# EN715_ExpansionBoard_ver1_1.net
KiCad netlist of a schematic drawn in EAGLE
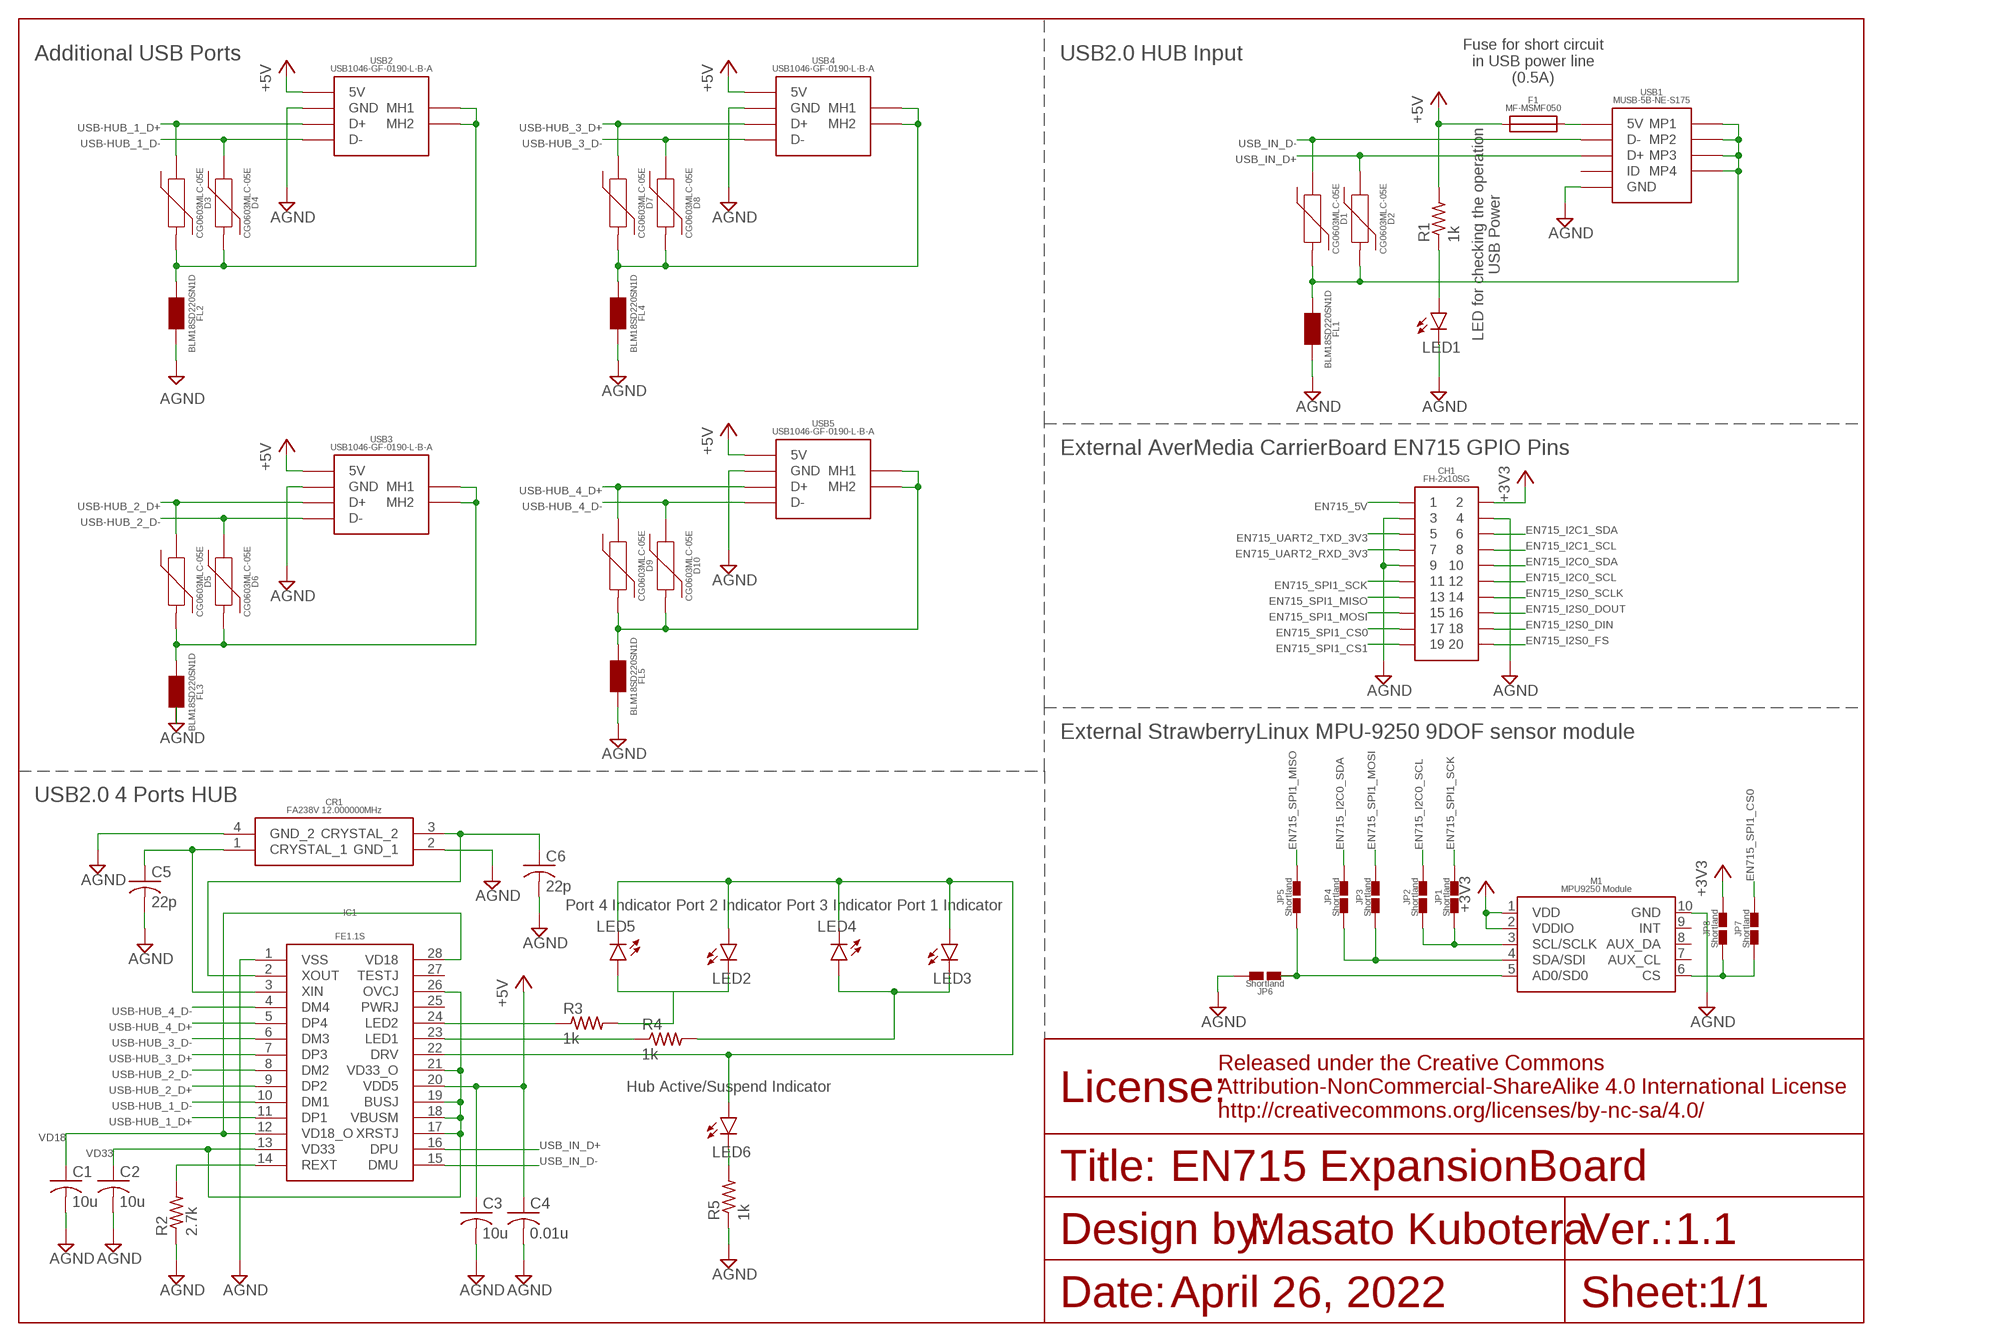
[diagram p0: schematic, sheet 1]

(export (version "E")
  (design (tool "Eeschema 10.0.6"))
  (components
    (comp (ref "C1")
      (value "10u")
      (footprint "eagle-import:C0603")
      (libsource (lib "eagle-import") (part "C-USC0603"))
    )
    (comp (ref "C2")
      (value "10u")
      (footprint "eagle-import:C0603")
      (libsource (lib "eagle-import") (part "C-USC0603"))
    )
    (comp (ref "C3")
      (value "10u")
      (footprint "eagle-import:C0603")
      (libsource (lib "eagle-import") (part "C-USC0603"))
    )
    (comp (ref "C4")
      (value "0.01u")
      (footprint "eagle-import:C0603")
      (libsource (lib "eagle-import") (part "C-USC0603"))
    )
    (comp (ref "C5")
      (value "22p")
      (footprint "eagle-import:C0603")
      (libsource (lib "eagle-import") (part "C-USC0603"))
    )
    (comp (ref "C6")
      (value "22p")
      (footprint "eagle-import:C0603")
      (libsource (lib "eagle-import") (part "C-USC0603"))
    )
    (comp (ref "CH1")
      (value "2X10")
      (footprint "eagle-import:2X10")
      (libsource (lib "eagle-import") (part "2X10"))
    )
    (comp (ref "CR1")
      (value "FA238V_12.000000MHZ")
      (footprint "eagle-import:FA238V")
      (libsource (lib "eagle-import") (part "FA238V_12.000000MHZ"))
    )
    (comp (ref "D1")
      (value "CG0603MLC-05E")
      (footprint "eagle-import:CG0603MLC-05E")
      (libsource (lib "eagle-import") (part "CG0603MLC-05E"))
    )
    (comp (ref "D2")
      (value "CG0603MLC-05E")
      (footprint "eagle-import:CG0603MLC-05E")
      (libsource (lib "eagle-import") (part "CG0603MLC-05E"))
    )
    (comp (ref "D3")
      (value "CG0603MLC-05E")
      (footprint "eagle-import:CG0603MLC-05E")
      (libsource (lib "eagle-import") (part "CG0603MLC-05E"))
    )
    (comp (ref "D4")
      (value "CG0603MLC-05E")
      (footprint "eagle-import:CG0603MLC-05E")
      (libsource (lib "eagle-import") (part "CG0603MLC-05E"))
    )
    (comp (ref "D5")
      (value "CG0603MLC-05E")
      (footprint "eagle-import:CG0603MLC-05E")
      (libsource (lib "eagle-import") (part "CG0603MLC-05E"))
    )
    (comp (ref "D6")
      (value "CG0603MLC-05E")
      (footprint "eagle-import:CG0603MLC-05E")
      (libsource (lib "eagle-import") (part "CG0603MLC-05E"))
    )
    (comp (ref "D7")
      (value "CG0603MLC-05E")
      (footprint "eagle-import:CG0603MLC-05E")
      (libsource (lib "eagle-import") (part "CG0603MLC-05E"))
    )
    (comp (ref "D8")
      (value "CG0603MLC-05E")
      (footprint "eagle-import:CG0603MLC-05E")
      (libsource (lib "eagle-import") (part "CG0603MLC-05E"))
    )
    (comp (ref "D9")
      (value "CG0603MLC-05E")
      (footprint "eagle-import:CG0603MLC-05E")
      (libsource (lib "eagle-import") (part "CG0603MLC-05E"))
    )
    (comp (ref "D10")
      (value "CG0603MLC-05E")
      (footprint "eagle-import:CG0603MLC-05E")
      (libsource (lib "eagle-import") (part "CG0603MLC-05E"))
    )
    (comp (ref "F1")
      (value "MF-MSMF050")
      (footprint "eagle-import:MF-MSMF050")
      (libsource (lib "eagle-import") (part "MF-MSMF050"))
    )
    (comp (ref "FL1")
      (value "BLM18SD220SN1D")
      (footprint "eagle-import:BLM18SD220SN1D")
      (libsource (lib "eagle-import") (part "BLM18SD220SN1D"))
    )
    (comp (ref "FL2")
      (value "BLM18SD220SN1D")
      (footprint "eagle-import:BLM18SD220SN1D")
      (libsource (lib "eagle-import") (part "BLM18SD220SN1D"))
    )
    (comp (ref "FL3")
      (value "BLM18SD220SN1D")
      (footprint "eagle-import:BLM18SD220SN1D")
      (libsource (lib "eagle-import") (part "BLM18SD220SN1D"))
    )
    (comp (ref "FL4")
      (value "BLM18SD220SN1D")
      (footprint "eagle-import:BLM18SD220SN1D")
      (libsource (lib "eagle-import") (part "BLM18SD220SN1D"))
    )
    (comp (ref "FL5")
      (value "BLM18SD220SN1D")
      (footprint "eagle-import:BLM18SD220SN1D")
      (libsource (lib "eagle-import") (part "BLM18SD220SN1D"))
    )
    (comp (ref "IC1")
      (value "FE1.1S")
      (footprint "eagle-import:FE1.1S")
      (libsource (lib "eagle-import") (part "FE1.1S"))
    )
    (comp (ref "JP1")
      (value "SHORTLAND")
      (footprint "eagle-import:SHORTLAND")
      (libsource (lib "eagle-import") (part "SHORTLAND"))
    )
    (comp (ref "JP2")
      (value "SHORTLAND")
      (footprint "eagle-import:SHORTLAND")
      (libsource (lib "eagle-import") (part "SHORTLAND"))
    )
    (comp (ref "JP3")
      (value "SHORTLAND")
      (footprint "eagle-import:SHORTLAND")
      (libsource (lib "eagle-import") (part "SHORTLAND"))
    )
    (comp (ref "JP4")
      (value "SHORTLAND")
      (footprint "eagle-import:SHORTLAND")
      (libsource (lib "eagle-import") (part "SHORTLAND"))
    )
    (comp (ref "JP5")
      (value "SHORTLAND")
      (footprint "eagle-import:SHORTLAND")
      (libsource (lib "eagle-import") (part "SHORTLAND"))
    )
    (comp (ref "JP6")
      (value "SHORTLAND")
      (footprint "eagle-import:SHORTLAND")
      (libsource (lib "eagle-import") (part "SHORTLAND"))
    )
    (comp (ref "JP7")
      (value "SHORTLAND")
      (footprint "eagle-import:SHORTLAND")
      (libsource (lib "eagle-import") (part "SHORTLAND"))
    )
    (comp (ref "JP8")
      (value "SHORTLAND")
      (footprint "eagle-import:SHORTLAND")
      (libsource (lib "eagle-import") (part "SHORTLAND"))
    )
    (comp (ref "LED1")
      (value "LEDSML0603")
      (footprint "eagle-import:SML0603")
      (libsource (lib "eagle-import") (part "LEDSML0603"))
    )
    (comp (ref "LED2")
      (value "LEDSML0603")
      (footprint "eagle-import:SML0603")
      (libsource (lib "eagle-import") (part "LEDSML0603"))
    )
    (comp (ref "LED3")
      (value "LEDSML0603")
      (footprint "eagle-import:SML0603")
      (libsource (lib "eagle-import") (part "LEDSML0603"))
    )
    (comp (ref "LED4")
      (value "LEDSML0603")
      (footprint "eagle-import:SML0603")
      (libsource (lib "eagle-import") (part "LEDSML0603"))
    )
    (comp (ref "LED5")
      (value "LEDSML0603")
      (footprint "eagle-import:SML0603")
      (libsource (lib "eagle-import") (part "LEDSML0603"))
    )
    (comp (ref "LED6")
      (value "LEDSML0603")
      (footprint "eagle-import:SML0603")
      (libsource (lib "eagle-import") (part "LEDSML0603"))
    )
    (comp (ref "M1")
      (value "MPU9250_MODULE")
      (footprint "eagle-import:MPU9250_MODULE")
      (libsource (lib "eagle-import") (part "MPU9250_MODULE"))
    )
    (comp (ref "R1")
      (value "1k")
      (footprint "eagle-import:R0603")
      (libsource (lib "eagle-import") (part "R-US_R0603"))
    )
    (comp (ref "R2")
      (value "2.7k")
      (footprint "eagle-import:R0603")
      (libsource (lib "eagle-import") (part "R-US_R0603"))
    )
    (comp (ref "R3")
      (value "1k")
      (footprint "eagle-import:R0603")
      (libsource (lib "eagle-import") (part "R-US_R0603"))
    )
    (comp (ref "R4")
      (value "1k")
      (footprint "eagle-import:R0603")
      (libsource (lib "eagle-import") (part "R-US_R0603"))
    )
    (comp (ref "R5")
      (value "1k")
      (footprint "eagle-import:R0603")
      (libsource (lib "eagle-import") (part "R-US_R0603"))
    )
    (comp (ref "USB1")
      (value "MINI_USB_B_SMD")
      (footprint "eagle-import:MINI_USB_B_SMD")
      (libsource (lib "eagle-import") (part "MINI_USB_B_SMD"))
    )
    (comp (ref "USB2")
      (value "USB_A_X1_SMD")
      (footprint "eagle-import:USB_A_X1_SMD")
      (libsource (lib "eagle-import") (part "USB_A_X1_SMD"))
    )
    (comp (ref "USB3")
      (value "USB_A_X1_SMD")
      (footprint "eagle-import:USB_A_X1_SMD")
      (libsource (lib "eagle-import") (part "USB_A_X1_SMD"))
    )
    (comp (ref "USB4")
      (value "USB_A_X1_SMD")
      (footprint "eagle-import:USB_A_X1_SMD")
      (libsource (lib "eagle-import") (part "USB_A_X1_SMD"))
    )
    (comp (ref "USB5")
      (value "USB_A_X1_SMD")
      (footprint "eagle-import:USB_A_X1_SMD")
      (libsource (lib "eagle-import") (part "USB_A_X1_SMD"))
    )
  )
  (nets
    (net (code "1") (name "+3V3") (class "Default")
      (node (ref "CH1") (pin "2") (pinfunction "2_2") (pintype "bidirectional"))
      (node (ref "JP8") (pin "2") (pinfunction "2_2") (pintype "bidirectional"))
      (node (ref "M1") (pin "1") (pinfunction "VDD_1") (pintype "bidirectional"))
      (node (ref "M1") (pin "2") (pinfunction "VDDIO_2") (pintype "bidirectional"))
    )
    (net (code "2") (name "+5V") (class "Default")
      (node (ref "C3") (pin "1") (pinfunction "1_1") (pintype "passive"))
      (node (ref "C4") (pin "1") (pinfunction "1_1") (pintype "passive"))
      (node (ref "F1") (pin "1") (pinfunction "1_1") (pintype "bidirectional"))
      (node (ref "IC1") (pin "20") (pinfunction "VDD5_20") (pintype "bidirectional"))
      (node (ref "R1") (pin "2") (pinfunction "2_2") (pintype "passive"))
      (node (ref "USB2") (pin "1") (pinfunction "5V_1") (pintype "bidirectional"))
      (node (ref "USB3") (pin "1") (pinfunction "5V_1") (pintype "bidirectional"))
      (node (ref "USB4") (pin "1") (pinfunction "5V_1") (pintype "bidirectional"))
      (node (ref "USB5") (pin "1") (pinfunction "5V_1") (pintype "bidirectional"))
    )
    (net (code "3") (name "/EN715_5V") (class "Default")
      (node (ref "CH1") (pin "1") (pinfunction "1_1") (pintype "bidirectional"))
    )
    (net (code "4") (name "/EN715_I2C0_SCL") (class "Default")
      (node (ref "CH1") (pin "12") (pinfunction "12_12") (pintype "bidirectional"))
      (node (ref "JP2") (pin "2") (pinfunction "2_2") (pintype "bidirectional"))
    )
    (net (code "5") (name "/EN715_I2C0_SDA") (class "Default")
      (node (ref "CH1") (pin "10") (pinfunction "10_10") (pintype "bidirectional"))
      (node (ref "JP4") (pin "2") (pinfunction "2_2") (pintype "bidirectional"))
    )
    (net (code "6") (name "/EN715_I2C1_SCL") (class "Default")
      (node (ref "CH1") (pin "8") (pinfunction "8_8") (pintype "bidirectional"))
    )
    (net (code "7") (name "/EN715_I2C1_SDA") (class "Default")
      (node (ref "CH1") (pin "6") (pinfunction "6_6") (pintype "bidirectional"))
    )
    (net (code "8") (name "/EN715_I2S0_DIN") (class "Default")
      (node (ref "CH1") (pin "18") (pinfunction "18_18") (pintype "bidirectional"))
    )
    (net (code "9") (name "/EN715_I2S0_DOUT") (class "Default")
      (node (ref "CH1") (pin "16") (pinfunction "16_16") (pintype "bidirectional"))
    )
    (net (code "10") (name "/EN715_I2S0_FS") (class "Default")
      (node (ref "CH1") (pin "20") (pinfunction "20_20") (pintype "bidirectional"))
    )
    (net (code "11") (name "/EN715_I2S0_SCLK") (class "Default")
      (node (ref "CH1") (pin "14") (pinfunction "14_14") (pintype "bidirectional"))
    )
    (net (code "12") (name "/EN715_SPI1_CS0") (class "Default")
      (node (ref "CH1") (pin "17") (pinfunction "17_17") (pintype "bidirectional"))
      (node (ref "JP7") (pin "2") (pinfunction "2_2") (pintype "bidirectional"))
    )
    (net (code "13") (name "/EN715_SPI1_CS1") (class "Default")
      (node (ref "CH1") (pin "19") (pinfunction "19_19") (pintype "bidirectional"))
    )
    (net (code "14") (name "/EN715_SPI1_MISO") (class "Default")
      (node (ref "CH1") (pin "13") (pinfunction "13_13") (pintype "bidirectional"))
      (node (ref "JP5") (pin "2") (pinfunction "2_2") (pintype "bidirectional"))
    )
    (net (code "15") (name "/EN715_SPI1_MOSI") (class "Default")
      (node (ref "CH1") (pin "15") (pinfunction "15_15") (pintype "bidirectional"))
      (node (ref "JP3") (pin "2") (pinfunction "2_2") (pintype "bidirectional"))
    )
    (net (code "16") (name "/EN715_SPI1_SCK") (class "Default")
      (node (ref "CH1") (pin "11") (pinfunction "11_11") (pintype "bidirectional"))
      (node (ref "JP1") (pin "2") (pinfunction "2_2") (pintype "bidirectional"))
    )
    (net (code "17") (name "/EN715_UART2_RXD_3V3") (class "Default")
      (node (ref "CH1") (pin "7") (pinfunction "7_7") (pintype "bidirectional"))
    )
    (net (code "18") (name "/EN715_UART2_TXD_3V3") (class "Default")
      (node (ref "CH1") (pin "5") (pinfunction "5_5") (pintype "bidirectional"))
    )
    (net (code "19") (name "/USB-HUB_1_D+") (class "Default")
      (node (ref "D3") (pin "1") (pinfunction "1_1") (pintype "bidirectional"))
      (node (ref "IC1") (pin "11") (pinfunction "DP1_11") (pintype "bidirectional"))
      (node (ref "USB2") (pin "3") (pinfunction "D+_3") (pintype "bidirectional"))
    )
    (net (code "20") (name "/USB-HUB_1_D-") (class "Default")
      (node (ref "D4") (pin "1") (pinfunction "1_1") (pintype "bidirectional"))
      (node (ref "IC1") (pin "10") (pinfunction "DM1_10") (pintype "bidirectional"))
      (node (ref "USB2") (pin "2") (pinfunction "D-_2") (pintype "bidirectional"))
    )
    (net (code "21") (name "/USB-HUB_2_D+") (class "Default")
      (node (ref "D5") (pin "1") (pinfunction "1_1") (pintype "bidirectional"))
      (node (ref "IC1") (pin "9") (pinfunction "DP2_9") (pintype "bidirectional"))
      (node (ref "USB3") (pin "3") (pinfunction "D+_3") (pintype "bidirectional"))
    )
    (net (code "22") (name "/USB-HUB_2_D-") (class "Default")
      (node (ref "D6") (pin "1") (pinfunction "1_1") (pintype "bidirectional"))
      (node (ref "IC1") (pin "8") (pinfunction "DM2_8") (pintype "bidirectional"))
      (node (ref "USB3") (pin "2") (pinfunction "D-_2") (pintype "bidirectional"))
    )
    (net (code "23") (name "/USB-HUB_3_D+") (class "Default")
      (node (ref "D7") (pin "1") (pinfunction "1_1") (pintype "bidirectional"))
      (node (ref "IC1") (pin "7") (pinfunction "DP3_7") (pintype "bidirectional"))
      (node (ref "USB4") (pin "3") (pinfunction "D+_3") (pintype "bidirectional"))
    )
    (net (code "24") (name "/USB-HUB_3_D-") (class "Default")
      (node (ref "D8") (pin "1") (pinfunction "1_1") (pintype "bidirectional"))
      (node (ref "IC1") (pin "6") (pinfunction "DM3_6") (pintype "bidirectional"))
      (node (ref "USB4") (pin "2") (pinfunction "D-_2") (pintype "bidirectional"))
    )
    (net (code "25") (name "/USB-HUB_4_D+") (class "Default")
      (node (ref "D9") (pin "1") (pinfunction "1_1") (pintype "bidirectional"))
      (node (ref "IC1") (pin "5") (pinfunction "DP4_5") (pintype "bidirectional"))
      (node (ref "USB5") (pin "3") (pinfunction "D+_3") (pintype "bidirectional"))
    )
    (net (code "26") (name "/USB-HUB_4_D-") (class "Default")
      (node (ref "D10") (pin "1") (pinfunction "1_1") (pintype "bidirectional"))
      (node (ref "IC1") (pin "4") (pinfunction "DM4_4") (pintype "bidirectional"))
      (node (ref "USB5") (pin "2") (pinfunction "D-_2") (pintype "bidirectional"))
    )
    (net (code "27") (name "/USB_IN_D+") (class "Default")
      (node (ref "D2") (pin "1") (pinfunction "1_1") (pintype "bidirectional"))
      (node (ref "IC1") (pin "16") (pinfunction "DPU_16") (pintype "bidirectional"))
      (node (ref "USB1") (pin "3") (pinfunction "D+_3") (pintype "bidirectional"))
    )
    (net (code "28") (name "/USB_IN_D-") (class "Default")
      (node (ref "D1") (pin "1") (pinfunction "1_1") (pintype "bidirectional"))
      (node (ref "IC1") (pin "15") (pinfunction "DMU_15") (pintype "bidirectional"))
      (node (ref "USB1") (pin "2") (pinfunction "D-_2") (pintype "bidirectional"))
    )
    (net (code "29") (name "/VD18") (class "Default")
      (node (ref "C1") (pin "1") (pinfunction "1_1") (pintype "passive"))
      (node (ref "IC1") (pin "12") (pinfunction "VD18_O_12") (pintype "bidirectional"))
      (node (ref "IC1") (pin "28") (pinfunction "VD18_28") (pintype "bidirectional"))
    )
    (net (code "30") (name "/VD33") (class "Default")
      (node (ref "C2") (pin "1") (pinfunction "1_1") (pintype "passive"))
      (node (ref "IC1") (pin "13") (pinfunction "VD33_13") (pintype "bidirectional"))
      (node (ref "IC1") (pin "17") (pinfunction "XRSTJ_17") (pintype "bidirectional"))
      (node (ref "IC1") (pin "18") (pinfunction "VBUSM_18") (pintype "bidirectional"))
      (node (ref "IC1") (pin "19") (pinfunction "BUSJ_19") (pintype "bidirectional"))
      (node (ref "IC1") (pin "21") (pinfunction "VD33_O_21") (pintype "bidirectional"))
      (node (ref "IC1") (pin "26") (pinfunction "OVCJ_26") (pintype "bidirectional"))
    )
    (net (code "31") (name "AGND") (class "Default")
      (node (ref "C1") (pin "2") (pinfunction "2_2") (pintype "passive"))
      (node (ref "C2") (pin "2") (pinfunction "2_2") (pintype "passive"))
      (node (ref "C3") (pin "2") (pinfunction "2_2") (pintype "passive"))
      (node (ref "C4") (pin "2") (pinfunction "2_2") (pintype "passive"))
      (node (ref "C5") (pin "2") (pinfunction "2_2") (pintype "passive"))
      (node (ref "C6") (pin "2") (pinfunction "2_2") (pintype "passive"))
      (node (ref "CH1") (pin "3") (pinfunction "3_3") (pintype "bidirectional"))
      (node (ref "CH1") (pin "4") (pinfunction "4_4") (pintype "bidirectional"))
      (node (ref "CH1") (pin "9") (pinfunction "9_9") (pintype "bidirectional"))
      (node (ref "CR1") (pin "2") (pinfunction "GND_1_2") (pintype "bidirectional"))
      (node (ref "CR1") (pin "4") (pinfunction "GND_2_4") (pintype "bidirectional"))
      (node (ref "FL1") (pin "2") (pinfunction "2_2") (pintype "bidirectional"))
      (node (ref "FL2") (pin "2") (pinfunction "2_2") (pintype "bidirectional"))
      (node (ref "FL3") (pin "2") (pinfunction "2_2") (pintype "bidirectional"))
      (node (ref "FL4") (pin "2") (pinfunction "2_2") (pintype "bidirectional"))
      (node (ref "FL5") (pin "2") (pinfunction "2_2") (pintype "bidirectional"))
      (node (ref "IC1") (pin "1") (pinfunction "VSS_1") (pintype "bidirectional"))
      (node (ref "JP6") (pin "2") (pinfunction "2_2") (pintype "bidirectional"))
      (node (ref "LED1") (pin "C") (pinfunction "C_C") (pintype "passive"))
      (node (ref "M1") (pin "10") (pinfunction "GND_10") (pintype "bidirectional"))
      (node (ref "R2") (pin "1") (pinfunction "1_1") (pintype "passive"))
      (node (ref "R5") (pin "1") (pinfunction "1_1") (pintype "passive"))
      (node (ref "USB1") (pin "5") (pinfunction "GND_5") (pintype "bidirectional"))
      (node (ref "USB2") (pin "4") (pinfunction "GND_4") (pintype "bidirectional"))
      (node (ref "USB3") (pin "4") (pinfunction "GND_4") (pintype "bidirectional"))
      (node (ref "USB4") (pin "4") (pinfunction "GND_4") (pintype "bidirectional"))
      (node (ref "USB5") (pin "4") (pinfunction "GND_4") (pintype "bidirectional"))
    )
    (net (code "32") (name "Net-(CR1-CRYSTAL_1)") (class "Default")
      (node (ref "C5") (pin "1") (pinfunction "1_1") (pintype "passive"))
      (node (ref "CR1") (pin "1") (pinfunction "CRYSTAL_1_1") (pintype "bidirectional"))
      (node (ref "IC1") (pin "3") (pinfunction "XIN_3") (pintype "bidirectional"))
    )
    (net (code "33") (name "Net-(CR1-CRYSTAL_2)") (class "Default")
      (node (ref "C6") (pin "1") (pinfunction "1_1") (pintype "passive"))
      (node (ref "CR1") (pin "3") (pinfunction "CRYSTAL_2_3") (pintype "bidirectional"))
      (node (ref "IC1") (pin "2") (pinfunction "XOUT_2") (pintype "bidirectional"))
    )
    (net (code "34") (name "Net-(D1-Pad2)") (class "Default")
      (node (ref "D1") (pin "2") (pinfunction "2_2") (pintype "bidirectional"))
      (node (ref "D2") (pin "2") (pinfunction "2_2") (pintype "bidirectional"))
      (node (ref "FL1") (pin "1") (pinfunction "1_1") (pintype "bidirectional"))
      (node (ref "USB1") (pin "MP1") (pinfunction "MP1_MP1") (pintype "bidirectional"))
      (node (ref "USB1") (pin "MP2") (pinfunction "MP2_MP2") (pintype "bidirectional"))
      (node (ref "USB1") (pin "MP3") (pinfunction "MP3_MP3") (pintype "bidirectional"))
      (node (ref "USB1") (pin "MP4") (pinfunction "MP4_MP4") (pintype "bidirectional"))
    )
    (net (code "35") (name "Net-(D3-Pad2)") (class "Default")
      (node (ref "D3") (pin "2") (pinfunction "2_2") (pintype "bidirectional"))
      (node (ref "D4") (pin "2") (pinfunction "2_2") (pintype "bidirectional"))
      (node (ref "FL2") (pin "1") (pinfunction "1_1") (pintype "bidirectional"))
      (node (ref "USB2") (pin "MH1") (pinfunction "MH1_MH1") (pintype "bidirectional"))
      (node (ref "USB2") (pin "MH2") (pinfunction "MH2_MH2") (pintype "bidirectional"))
    )
    (net (code "36") (name "Net-(D5-Pad2)") (class "Default")
      (node (ref "D5") (pin "2") (pinfunction "2_2") (pintype "bidirectional"))
      (node (ref "D6") (pin "2") (pinfunction "2_2") (pintype "bidirectional"))
      (node (ref "FL3") (pin "1") (pinfunction "1_1") (pintype "bidirectional"))
      (node (ref "USB3") (pin "MH1") (pinfunction "MH1_MH1") (pintype "bidirectional"))
      (node (ref "USB3") (pin "MH2") (pinfunction "MH2_MH2") (pintype "bidirectional"))
    )
    (net (code "37") (name "Net-(D7-Pad2)") (class "Default")
      (node (ref "D7") (pin "2") (pinfunction "2_2") (pintype "bidirectional"))
      (node (ref "D8") (pin "2") (pinfunction "2_2") (pintype "bidirectional"))
      (node (ref "FL4") (pin "1") (pinfunction "1_1") (pintype "bidirectional"))
      (node (ref "USB4") (pin "MH1") (pinfunction "MH1_MH1") (pintype "bidirectional"))
      (node (ref "USB4") (pin "MH2") (pinfunction "MH2_MH2") (pintype "bidirectional"))
    )
    (net (code "38") (name "Net-(D10-Pad2)") (class "Default")
      (node (ref "D10") (pin "2") (pinfunction "2_2") (pintype "bidirectional"))
      (node (ref "D9") (pin "2") (pinfunction "2_2") (pintype "bidirectional"))
      (node (ref "FL5") (pin "1") (pinfunction "1_1") (pintype "bidirectional"))
      (node (ref "USB5") (pin "MH1") (pinfunction "MH1_MH1") (pintype "bidirectional"))
      (node (ref "USB5") (pin "MH2") (pinfunction "MH2_MH2") (pintype "bidirectional"))
    )
    (net (code "39") (name "Net-(IC1-DRV)") (class "Default")
      (node (ref "IC1") (pin "22") (pinfunction "DRV_22") (pintype "bidirectional"))
      (node (ref "LED2") (pin "A") (pinfunction "A_A") (pintype "passive"))
      (node (ref "LED3") (pin "A") (pinfunction "A_A") (pintype "passive"))
      (node (ref "LED4") (pin "C") (pinfunction "C_C") (pintype "passive"))
      (node (ref "LED5") (pin "C") (pinfunction "C_C") (pintype "passive"))
      (node (ref "LED6") (pin "A") (pinfunction "A_A") (pintype "passive"))
    )
    (net (code "40") (name "Net-(IC1-LED1)") (class "Default")
      (node (ref "IC1") (pin "23") (pinfunction "LED1_23") (pintype "bidirectional"))
      (node (ref "R4") (pin "1") (pinfunction "1_1") (pintype "passive"))
    )
    (net (code "41") (name "Net-(IC1-LED2)") (class "Default")
      (node (ref "IC1") (pin "24") (pinfunction "LED2_24") (pintype "bidirectional"))
      (node (ref "R3") (pin "1") (pinfunction "1_1") (pintype "passive"))
    )
    (net (code "42") (name "Net-(IC1-REXT)") (class "Default")
      (node (ref "IC1") (pin "14") (pinfunction "REXT_14") (pintype "bidirectional"))
      (node (ref "R2") (pin "2") (pinfunction "2_2") (pintype "passive"))
    )
    (net (code "43") (name "Net-(LED1-PadA)") (class "Default")
      (node (ref "LED1") (pin "A") (pinfunction "A_A") (pintype "passive"))
      (node (ref "R1") (pin "1") (pinfunction "1_1") (pintype "passive"))
    )
    (net (code "44") (name "Net-(LED2-PadC)") (class "Default")
      (node (ref "LED2") (pin "C") (pinfunction "C_C") (pintype "passive"))
      (node (ref "LED5") (pin "A") (pinfunction "A_A") (pintype "passive"))
      (node (ref "R3") (pin "2") (pinfunction "2_2") (pintype "passive"))
    )
    (net (code "45") (name "Net-(LED3-PadC)") (class "Default")
      (node (ref "LED3") (pin "C") (pinfunction "C_C") (pintype "passive"))
      (node (ref "LED4") (pin "A") (pinfunction "A_A") (pintype "passive"))
      (node (ref "R4") (pin "2") (pinfunction "2_2") (pintype "passive"))
    )
    (net (code "46") (name "Net-(LED6-PadC)") (class "Default")
      (node (ref "LED6") (pin "C") (pinfunction "C_C") (pintype "passive"))
      (node (ref "R5") (pin "2") (pinfunction "2_2") (pintype "passive"))
    )
    (net (code "47") (name "Net-(M1-AD0{slash}SD0)") (class "Default")
      (node (ref "JP5") (pin "1") (pinfunction "1_1") (pintype "bidirectional"))
      (node (ref "JP6") (pin "1") (pinfunction "1_1") (pintype "bidirectional"))
      (node (ref "M1") (pin "5") (pinfunction "AD0/SD0_5") (pintype "bidirectional"))
    )
    (net (code "48") (name "Net-(M1-CS)") (class "Default")
      (node (ref "JP7") (pin "1") (pinfunction "1_1") (pintype "bidirectional"))
      (node (ref "JP8") (pin "1") (pinfunction "1_1") (pintype "bidirectional"))
      (node (ref "M1") (pin "6") (pinfunction "CS_6") (pintype "bidirectional"))
    )
    (net (code "49") (name "Net-(M1-SCL{slash}SCLK)") (class "Default")
      (node (ref "JP1") (pin "1") (pinfunction "1_1") (pintype "bidirectional"))
      (node (ref "JP2") (pin "1") (pinfunction "1_1") (pintype "bidirectional"))
      (node (ref "M1") (pin "3") (pinfunction "SCL/SCLK_3") (pintype "bidirectional"))
    )
    (net (code "50") (name "Net-(M1-SDA{slash}SDI)") (class "Default")
      (node (ref "JP3") (pin "1") (pinfunction "1_1") (pintype "bidirectional"))
      (node (ref "JP4") (pin "1") (pinfunction "1_1") (pintype "bidirectional"))
      (node (ref "M1") (pin "4") (pinfunction "SDA/SDI_4") (pintype "bidirectional"))
    )
    (net (code "51") (name "Net-(USB1-5V)") (class "Default")
      (node (ref "F1") (pin "2") (pinfunction "2_2") (pintype "bidirectional"))
      (node (ref "USB1") (pin "1") (pinfunction "5V_1") (pintype "bidirectional"))
    )
    (net (code "52") (name "unconnected-(IC1-PWRJ-Pad25)") (class "Default")
      (node (ref "IC1") (pin "25") (pinfunction "PWRJ_25") (pintype "bidirectional"))
    )
    (net (code "53") (name "unconnected-(IC1-TESTJ-Pad27)") (class "Default")
      (node (ref "IC1") (pin "27") (pinfunction "TESTJ_27") (pintype "bidirectional"))
    )
    (net (code "54") (name "unconnected-(M1-AUX_CL-Pad7)") (class "Default")
      (node (ref "M1") (pin "7") (pinfunction "AUX_CL_7") (pintype "bidirectional"))
    )
    (net (code "55") (name "unconnected-(M1-AUX_DA-Pad8)") (class "Default")
      (node (ref "M1") (pin "8") (pinfunction "AUX_DA_8") (pintype "bidirectional"))
    )
    (net (code "56") (name "unconnected-(M1-INT-Pad9)") (class "Default")
      (node (ref "M1") (pin "9") (pinfunction "INT_9") (pintype "bidirectional"))
    )
    (net (code "57") (name "unconnected-(USB1-ID-Pad4)") (class "Default")
      (node (ref "USB1") (pin "4") (pinfunction "ID_4") (pintype "bidirectional"))
    )
  )
)
